# Rover-2_Power_Supply.net
KiCad netlist of a schematic drawn in EAGLE
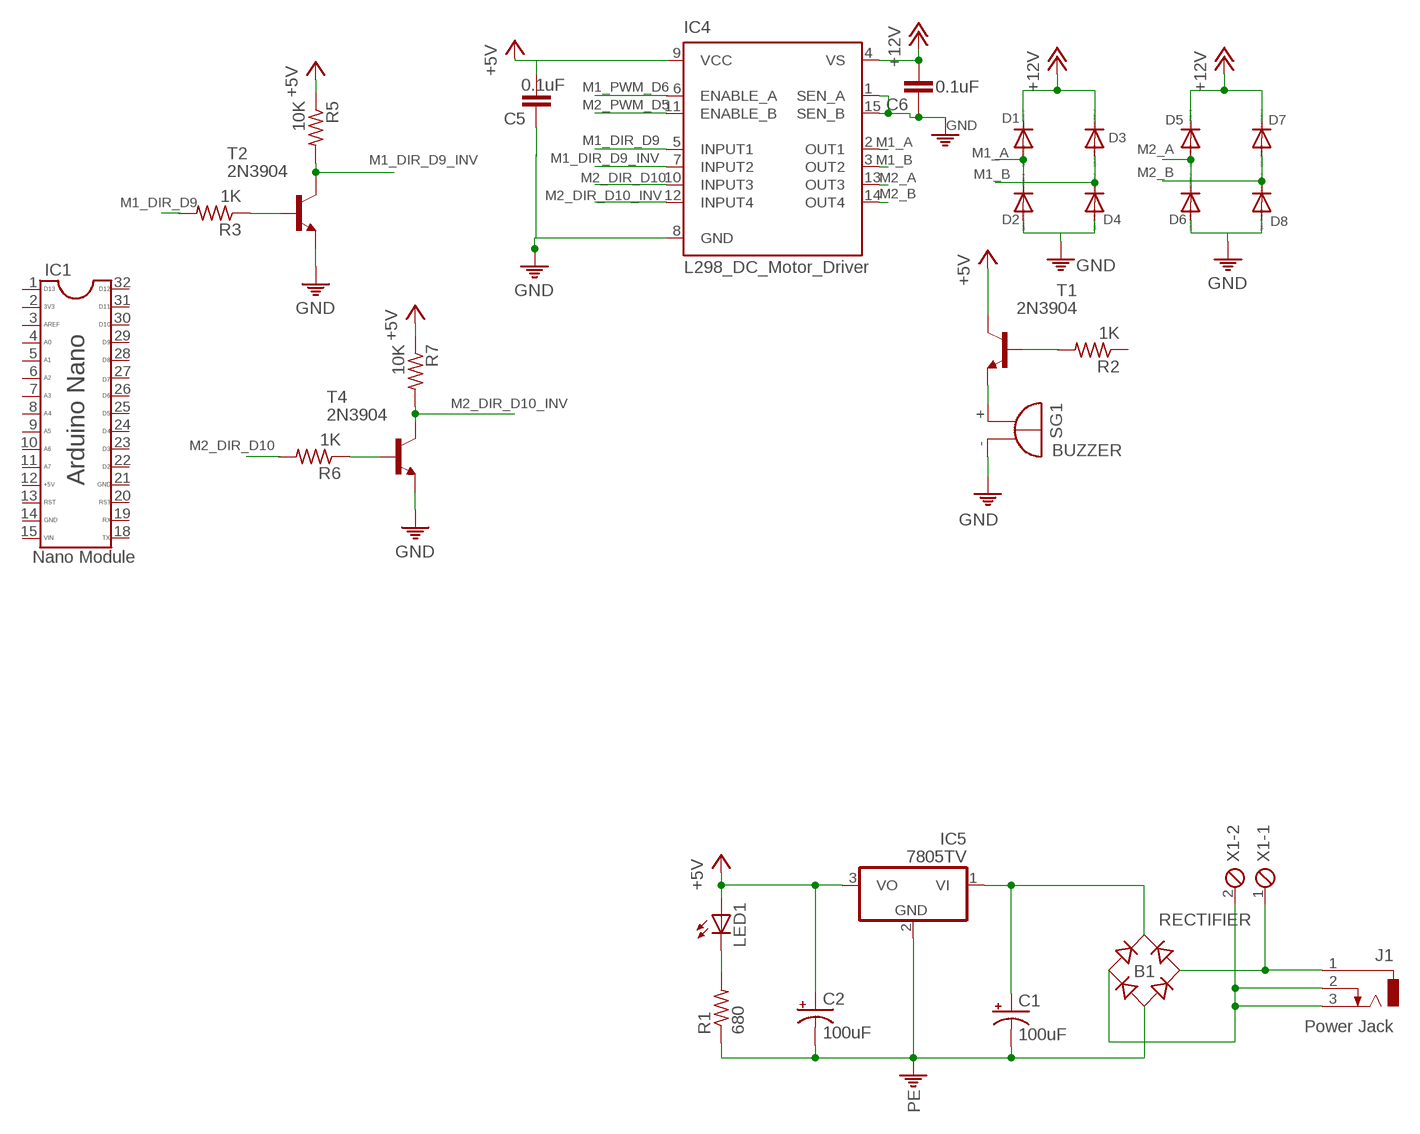
[diagram p0: schematic, sheet 1]

(export (version "E")
  (design (tool "Eeschema 10.0.6"))
  (components
    (comp (ref "B1")
      (value "RECTIFIER")
      (footprint "eagle-import:RB1A")
      (libsource (lib "eagle-import") (part "RB1A"))
    )
    (comp (ref "C1")
      (value "100uF")
      (footprint "eagle-import:E5-8,5")
      (libsource (lib "eagle-import") (part "CPOL-USE5-8.5"))
    )
    (comp (ref "C2")
      (value "100uF")
      (footprint "eagle-import:E5-8,5")
      (libsource (lib "eagle-import") (part "CPOL-USE5-8.5"))
    )
    (comp (ref "C5")
      (value "0.1uF")
      (footprint "eagle-import:C025-024X044")
      (libsource (lib "eagle-import") (part "C-EU025-024X044"))
    )
    (comp (ref "C6")
      (value "0.1uF")
      (footprint "eagle-import:C025-024X044")
      (libsource (lib "eagle-import") (part "C-EU025-024X044"))
    )
    (comp (ref "D1")
      (value "DIODE-D-2.5")
      (footprint "eagle-import:D-2.5")
      (libsource (lib "eagle-import") (part "DIODE-D-2.5"))
    )
    (comp (ref "D2")
      (value "DIODE-D-2.5")
      (footprint "eagle-import:D-2.5")
      (libsource (lib "eagle-import") (part "DIODE-D-2.5"))
    )
    (comp (ref "D3")
      (value "DIODE-D-2.5")
      (footprint "eagle-import:D-2.5")
      (libsource (lib "eagle-import") (part "DIODE-D-2.5"))
    )
    (comp (ref "D4")
      (value "DIODE-D-2.5")
      (footprint "eagle-import:D-2.5")
      (libsource (lib "eagle-import") (part "DIODE-D-2.5"))
    )
    (comp (ref "D5")
      (value "DIODE-D-2.5")
      (footprint "eagle-import:D-2.5")
      (libsource (lib "eagle-import") (part "DIODE-D-2.5"))
    )
    (comp (ref "D6")
      (value "DIODE-D-2.5")
      (footprint "eagle-import:D-2.5")
      (libsource (lib "eagle-import") (part "DIODE-D-2.5"))
    )
    (comp (ref "D7")
      (value "DIODE-D-2.5")
      (footprint "eagle-import:D-2.5")
      (libsource (lib "eagle-import") (part "DIODE-D-2.5"))
    )
    (comp (ref "D8")
      (value "DIODE-D-2.5")
      (footprint "eagle-import:D-2.5")
      (libsource (lib "eagle-import") (part "DIODE-D-2.5"))
    )
    (comp (ref "IC1")
      (value "Nano Module")
      (footprint "eagle-import:DIL32")
      (libsource (lib "eagle-import") (part "DIL32"))
    )
    (comp (ref "IC4")
      (value "L298_DC_Motor_Driver")
      (footprint "eagle-import:MULTIWATT-15")
      (fields (field (name "MPN") "L298N"))
      (libsource (lib "eagle-import") (part "L298"))
    )
    (comp (ref "IC5")
      (value "7805TV")
      (footprint "eagle-import:TO220V")
      (libsource (lib "eagle-import") (part "78TV05"))
    )
    (comp (ref "J1")
      (value "Power Jack")
      (footprint "eagle-import:ROVER-PW-JACL")
      (libsource (lib "eagle-import") (part "DCJ0303"))
    )
    (comp (ref "LED1")
      (value "LED3MM")
      (footprint "eagle-import:LED3MM")
      (libsource (lib "eagle-import") (part "LED3MM"))
    )
    (comp (ref "R1")
      (value "680")
      (footprint "eagle-import:0204_5")
      (libsource (lib "eagle-import") (part "R-US_0204/5"))
    )
    (comp (ref "R2")
      (value "1K")
      (footprint "eagle-import:0204_5")
      (libsource (lib "eagle-import") (part "R-US_0204/5"))
    )
    (comp (ref "R3")
      (value "1K")
      (footprint "eagle-import:0204_5")
      (libsource (lib "eagle-import") (part "R-US_0204/5"))
    )
    (comp (ref "R5")
      (value "10K")
      (footprint "eagle-import:0204_5")
      (libsource (lib "eagle-import") (part "R-US_0204/5"))
    )
    (comp (ref "R6")
      (value "1K")
      (footprint "eagle-import:0204_5")
      (libsource (lib "eagle-import") (part "R-US_0204/5"))
    )
    (comp (ref "R7")
      (value "10K")
      (footprint "eagle-import:0204_5")
      (libsource (lib "eagle-import") (part "R-US_0204/5"))
    )
    (comp (ref "SG1")
      (value "BUZZER")
      (footprint "eagle-import:EB2209A")
      (libsource (lib "eagle-import") (part "EB2209A"))
    )
    (comp (ref "T1")
      (value "2N3904")
      (footprint "eagle-import:TO92")
      (libsource (lib "eagle-import") (part "2N3904"))
    )
    (comp (ref "T2")
      (value "2N3904")
      (footprint "eagle-import:TO92")
      (libsource (lib "eagle-import") (part "2N3904"))
    )
    (comp (ref "T4")
      (value "2N3904")
      (footprint "eagle-import:TO92")
      (libsource (lib "eagle-import") (part "2N3904"))
    )
    (comp (ref "X1")
      (value "MPT2")
      (footprint "eagle-import:2POL254")
      (libsource (lib "eagle-import") (part "MPT2"))
    )
  )
  (nets
    (net (code "1") (name "+5V") (class "Default")
      (node (ref "C2") (pin "+") (pinfunction "+_+") (pintype "passive"))
      (node (ref "C5") (pin "2") (pinfunction "2_2") (pintype "passive"))
      (node (ref "IC5") (pin "3") (pinfunction "VO_3") (pintype "passive"))
      (node (ref "LED1") (pin "A") (pinfunction "A_A") (pintype "passive"))
      (node (ref "R5") (pin "1") (pinfunction "1_1") (pintype "passive"))
      (node (ref "R7") (pin "1") (pinfunction "1_1") (pintype "passive"))
      (node (ref "T1") (pin "1") (pinfunction "C_1") (pintype "passive"))
    )
    (net (code "2") (name "+12V") (class "Default")
      (node (ref "C6") (pin "2") (pinfunction "2_2") (pintype "passive"))
      (node (ref "D1") (pin "C") (pinfunction "C_C") (pintype "passive"))
      (node (ref "D3") (pin "C") (pinfunction "C_C") (pintype "passive"))
      (node (ref "D5") (pin "C") (pinfunction "C_C") (pintype "passive"))
      (node (ref "D7") (pin "C") (pinfunction "C_C") (pintype "passive"))
      (node (ref "IC4") (pin "4") (pinfunction "VS_4") (pintype "power_in"))
    )
    (net (code "3") (name "/M1_A") (class "Default")
      (node (ref "D1") (pin "A") (pinfunction "A_A") (pintype "passive"))
      (node (ref "D2") (pin "C") (pinfunction "C_C") (pintype "passive"))
      (node (ref "IC4") (pin "2") (pinfunction "OUT1_2") (pintype "output"))
    )
    (net (code "4") (name "/M1_B") (class "Default")
      (node (ref "D3") (pin "A") (pinfunction "A_A") (pintype "passive"))
      (node (ref "D4") (pin "C") (pinfunction "C_C") (pintype "passive"))
      (node (ref "IC4") (pin "3") (pinfunction "OUT2_3") (pintype "output"))
    )
    (net (code "5") (name "/M1_DIR_D9") (class "Default")
      (node (ref "IC4") (pin "5") (pinfunction "INPUT1_5") (pintype "input"))
    )
    (net (code "6") (name "/M1_DIR_D9_INV") (class "Default")
      (node (ref "IC4") (pin "7") (pinfunction "INPUT2_7") (pintype "input"))
      (node (ref "R5") (pin "2") (pinfunction "2_2") (pintype "passive"))
      (node (ref "T2") (pin "1") (pinfunction "C_1") (pintype "passive"))
    )
    (net (code "8") (name "/M2_A") (class "Default")
      (node (ref "D5") (pin "A") (pinfunction "A_A") (pintype "passive"))
      (node (ref "D6") (pin "C") (pinfunction "C_C") (pintype "passive"))
      (node (ref "IC4") (pin "13") (pinfunction "OUT3_13") (pintype "output"))
    )
    (net (code "9") (name "/M2_B") (class "Default")
      (node (ref "D7") (pin "A") (pinfunction "A_A") (pintype "passive"))
      (node (ref "D8") (pin "C") (pinfunction "C_C") (pintype "passive"))
      (node (ref "IC4") (pin "14") (pinfunction "OUT4_14") (pintype "output"))
    )
    (net (code "10") (name "/M2_DIR_D10") (class "Default")
      (node (ref "IC4") (pin "10") (pinfunction "INPUT3_10") (pintype "input"))
    )
    (net (code "11") (name "/M2_DIR_D10_INV") (class "Default")
      (node (ref "IC4") (pin "12") (pinfunction "INPUT4_12") (pintype "input"))
      (node (ref "R7") (pin "2") (pinfunction "2_2") (pintype "passive"))
      (node (ref "T4") (pin "1") (pinfunction "C_1") (pintype "passive"))
    )
    (net (code "12") (name "/M2_PWM_D5") (class "Default")
      (node (ref "IC4") (pin "11") (pinfunction "ENABLE_B_11") (pintype "input"))
    )
    (net (code "13") (name "/VCC") (class "Default")
      (node (ref "IC4") (pin "9") (pinfunction "VCC_9") (pintype "power_in"))
    )
    (net (code "14") (name "GND") (class "Default")
      (node (ref "B1") (pin "-") (pinfunction "-_-") (pintype "passive"))
      (node (ref "C1") (pin "-") (pinfunction "-_-") (pintype "passive"))
      (node (ref "C2") (pin "-") (pinfunction "-_-") (pintype "passive"))
      (node (ref "C6") (pin "1") (pinfunction "1_1") (pintype "passive"))
      (node (ref "D2") (pin "A") (pinfunction "A_A") (pintype "passive"))
      (node (ref "D4") (pin "A") (pinfunction "A_A") (pintype "passive"))
      (node (ref "D6") (pin "A") (pinfunction "A_A") (pintype "passive"))
      (node (ref "D8") (pin "A") (pinfunction "A_A") (pintype "passive"))
      (node (ref "IC4") (pin "1") (pinfunction "SEN_A_1") (pintype "input"))
      (node (ref "IC4") (pin "15") (pinfunction "SEN_B_15") (pintype "input"))
      (node (ref "IC4") (pin "8") (pinfunction "GND_8") (pintype "power_in"))
      (node (ref "IC5") (pin "2") (pinfunction "GND_2") (pintype "passive"))
      (node (ref "R1") (pin "1") (pinfunction "1_1") (pintype "passive"))
      (node (ref "SG1") (pin "-") (pinfunction "-_-") (pintype "passive"))
      (node (ref "T2") (pin "3") (pinfunction "E_3") (pintype "passive"))
      (node (ref "T4") (pin "3") (pinfunction "E_3") (pintype "passive"))
    )
    (net (code "15") (name "Net-(B1-PadAC1)") (class "Default")
      (node (ref "B1") (pin "AC1") (pinfunction "AC1_AC1") (pintype "passive"))
      (node (ref "J1") (pin "1") (pinfunction "1_1") (pintype "passive"))
      (node (ref "X1") (pin "1") (pinfunction "1_1") (pintype "passive"))
    )
    (net (code "16") (name "Net-(IC5-VI)") (class "Default")
      (node (ref "B1") (pin "+") (pinfunction "+_+") (pintype "passive"))
      (node (ref "C1") (pin "+") (pinfunction "+_+") (pintype "passive"))
      (node (ref "IC5") (pin "1") (pinfunction "VI_1") (pintype "input"))
    )
    (net (code "17") (name "Net-(LED1-C)") (class "Default")
      (node (ref "LED1") (pin "K") (pinfunction "C_K") (pintype "passive"))
      (node (ref "R1") (pin "2") (pinfunction "2_2") (pintype "passive"))
    )
    (net (code "18") (name "Net-(T1-E)") (class "Default")
      (node (ref "SG1") (pin "+") (pinfunction "+_+") (pintype "passive"))
      (node (ref "T1") (pin "3") (pinfunction "E_3") (pintype "passive"))
    )
    (net (code "19") (name "Net-(T2-B)") (class "Default")
      (node (ref "R3") (pin "1") (pinfunction "1_1") (pintype "passive"))
      (node (ref "T2") (pin "2") (pinfunction "B_2") (pintype "passive"))
    )
    (net (code "20") (name "Net-(T4-B)") (class "Default")
      (node (ref "R6") (pin "1") (pinfunction "1_1") (pintype "passive"))
      (node (ref "T4") (pin "2") (pinfunction "B_2") (pintype "passive"))
    )
    (net (code "21") (name "Net-(X1B-1)") (class "Default")
      (node (ref "B1") (pin "AC2") (pinfunction "AC2_AC2") (pintype "passive"))
      (node (ref "J1") (pin "2") (pinfunction "2_2") (pintype "passive"))
      (node (ref "J1") (pin "3") (pinfunction "3_3") (pintype "passive"))
      (node (ref "X1") (pin "2") (pinfunction "1_2") (pintype "passive"))
    )
    (net (code "22") (name "unconnected-(C5-Pad1)") (class "Default")
      (node (ref "C5") (pin "1") (pinfunction "1_1") (pintype "passive"))
    )
    (net (code "23") (name "unconnected-(IC1-3V3-Pad2)") (class "Default")
      (node (ref "IC1") (pin "2") (pinfunction "3V3_2") (pintype "passive"))
    )
    (net (code "24") (name "unconnected-(IC1-5V-Pad12)") (class "Default")
      (node (ref "IC1") (pin "12") (pinfunction "5V_12") (pintype "passive"))
    )
    (net (code "25") (name "unconnected-(IC1-A0{slash}D14-Pad4)") (class "Default")
      (node (ref "IC1") (pin "4") (pinfunction "A0/D14_4") (pintype "passive"))
    )
    (net (code "26") (name "unconnected-(IC1-A1{slash}D15-Pad5)") (class "Default")
      (node (ref "IC1") (pin "5") (pinfunction "A1/D15_5") (pintype "passive"))
    )
    (net (code "27") (name "unconnected-(IC1-A2{slash}D16-Pad6)") (class "Default")
      (node (ref "IC1") (pin "6") (pinfunction "A2/D16_6") (pintype "passive"))
    )
    (net (code "28") (name "unconnected-(IC1-A3{slash}D17-Pad7)") (class "Default")
      (node (ref "IC1") (pin "7") (pinfunction "A3/D17_7") (pintype "passive"))
    )
    (net (code "29") (name "unconnected-(IC1-A4{slash}D18{slash}SDA-Pad8)") (class "Default")
      (node (ref "IC1") (pin "8") (pinfunction "A4/D18/SDA_8") (pintype "passive"))
    )
    (net (code "30") (name "unconnected-(IC1-A5{slash}D19{slash}SCL-Pad9)") (class "Default")
      (node (ref "IC1") (pin "9") (pinfunction "A5/D19/SCL_9") (pintype "passive"))
    )
    (net (code "31") (name "unconnected-(IC1-A6-Pad10)") (class "Default")
      (node (ref "IC1") (pin "10") (pinfunction "A6_10") (pintype "passive"))
    )
    (net (code "32") (name "unconnected-(IC1-A7-Pad11)") (class "Default")
      (node (ref "IC1") (pin "11") (pinfunction "A7_11") (pintype "passive"))
    )
    (net (code "33") (name "unconnected-(IC1-AREF-Pad3)") (class "Default")
      (node (ref "IC1") (pin "3") (pinfunction "AREF_3") (pintype "passive"))
    )
    (net (code "34") (name "unconnected-(IC1-D2-Pad22)") (class "Default")
      (node (ref "IC1") (pin "22") (pinfunction "D2_22") (pintype "passive"))
    )
    (net (code "35") (name "unconnected-(IC1-D3-Pad23)") (class "Default")
      (node (ref "IC1") (pin "23") (pinfunction "D3_23") (pintype "passive"))
    )
    (net (code "36") (name "unconnected-(IC1-D4-Pad24)") (class "Default")
      (node (ref "IC1") (pin "24") (pinfunction "D4_24") (pintype "passive"))
    )
    (net (code "37") (name "unconnected-(IC1-D5{slash}PWM-Pad25)") (class "Default")
      (node (ref "IC1") (pin "25") (pinfunction "D5/PWM_25") (pintype "passive"))
    )
    (net (code "38") (name "unconnected-(IC1-D6{slash}PWM-Pad26)") (class "Default")
      (node (ref "IC1") (pin "26") (pinfunction "D6/PWM_26") (pintype "passive"))
    )
    (net (code "39") (name "unconnected-(IC1-D7-Pad27)") (class "Default")
      (node (ref "IC1") (pin "27") (pinfunction "D7_27") (pintype "passive"))
    )
    (net (code "40") (name "unconnected-(IC1-D8-Pad28)") (class "Default")
      (node (ref "IC1") (pin "28") (pinfunction "D8_28") (pintype "passive"))
    )
    (net (code "41") (name "unconnected-(IC1-D9{slash}PWM-Pad29)") (class "Default")
      (node (ref "IC1") (pin "29") (pinfunction "D9/PWM_29") (pintype "passive"))
    )
    (net (code "42") (name "unconnected-(IC1-D10{slash}PWM-Pad30)") (class "Default")
      (node (ref "IC1") (pin "30") (pinfunction "D10/PWM_30") (pintype "passive"))
    )
    (net (code "43") (name "unconnected-(IC1-D11{slash}MOSI-Pad31)") (class "Default")
      (node (ref "IC1") (pin "31") (pinfunction "D11/MOSI_31") (pintype "passive"))
    )
    (net (code "44") (name "unconnected-(IC1-D12{slash}MISO-Pad32)") (class "Default")
      (node (ref "IC1") (pin "32") (pinfunction "D12/MISO_32") (pintype "passive"))
    )
    (net (code "45") (name "unconnected-(IC1-D13-Pad1)") (class "Default")
      (node (ref "IC1") (pin "1") (pinfunction "D13_1") (pintype "passive"))
    )
    (net (code "46") (name "unconnected-(IC1-GND1-Pad14)") (class "Default")
      (node (ref "IC1") (pin "14") (pinfunction "GND1_14") (pintype "passive"))
    )
    (net (code "47") (name "unconnected-(IC1-GND2-Pad21)") (class "Default")
      (node (ref "IC1") (pin "21") (pinfunction "GND2_21") (pintype "passive"))
    )
    (net (code "48") (name "unconnected-(IC1-RST1-Pad13)") (class "Default")
      (node (ref "IC1") (pin "13") (pinfunction "RST1_13") (pintype "passive"))
    )
    (net (code "49") (name "unconnected-(IC1-RST2-Pad20)") (class "Default")
      (node (ref "IC1") (pin "20") (pinfunction "RST2_20") (pintype "passive"))
    )
    (net (code "50") (name "unconnected-(IC1-RX-Pad19)") (class "Default")
      (node (ref "IC1") (pin "19") (pinfunction "RX_19") (pintype "passive"))
    )
    (net (code "51") (name "unconnected-(IC1-TX-Pad18)") (class "Default")
      (node (ref "IC1") (pin "18") (pinfunction "TX_18") (pintype "passive"))
    )
    (net (code "52") (name "unconnected-(IC1-VIN-Pad15)") (class "Default")
      (node (ref "IC1") (pin "15") (pinfunction "VIN_15") (pintype "passive"))
    )
    (net (code "53") (name "unconnected-(IC4-ENABLE_A-Pad6)") (class "Default")
      (node (ref "IC4") (pin "6") (pinfunction "ENABLE_A_6") (pintype "input"))
    )
    (net (code "54") (name "unconnected-(R2-Pad1)") (class "Default")
      (node (ref "R2") (pin "1") (pinfunction "1_1") (pintype "passive"))
    )
    (net (code "55") (name "unconnected-(R2-Pad2)") (class "Default")
      (node (ref "R2") (pin "2") (pinfunction "2_2") (pintype "passive"))
    )
    (net (code "56") (name "unconnected-(R3-Pad2)") (class "Default")
      (node (ref "R3") (pin "2") (pinfunction "2_2") (pintype "passive"))
    )
    (net (code "57") (name "unconnected-(R6-Pad2)") (class "Default")
      (node (ref "R6") (pin "2") (pinfunction "2_2") (pintype "passive"))
    )
    (net (code "58") (name "unconnected-(T1-B-Pad2)") (class "Default")
      (node (ref "T1") (pin "2") (pinfunction "B_2") (pintype "passive"))
    )
  )
)
